# Full_Water_Level_Detector_Project_Schema.net
KiCad netlist of a schematic drawn in EAGLE
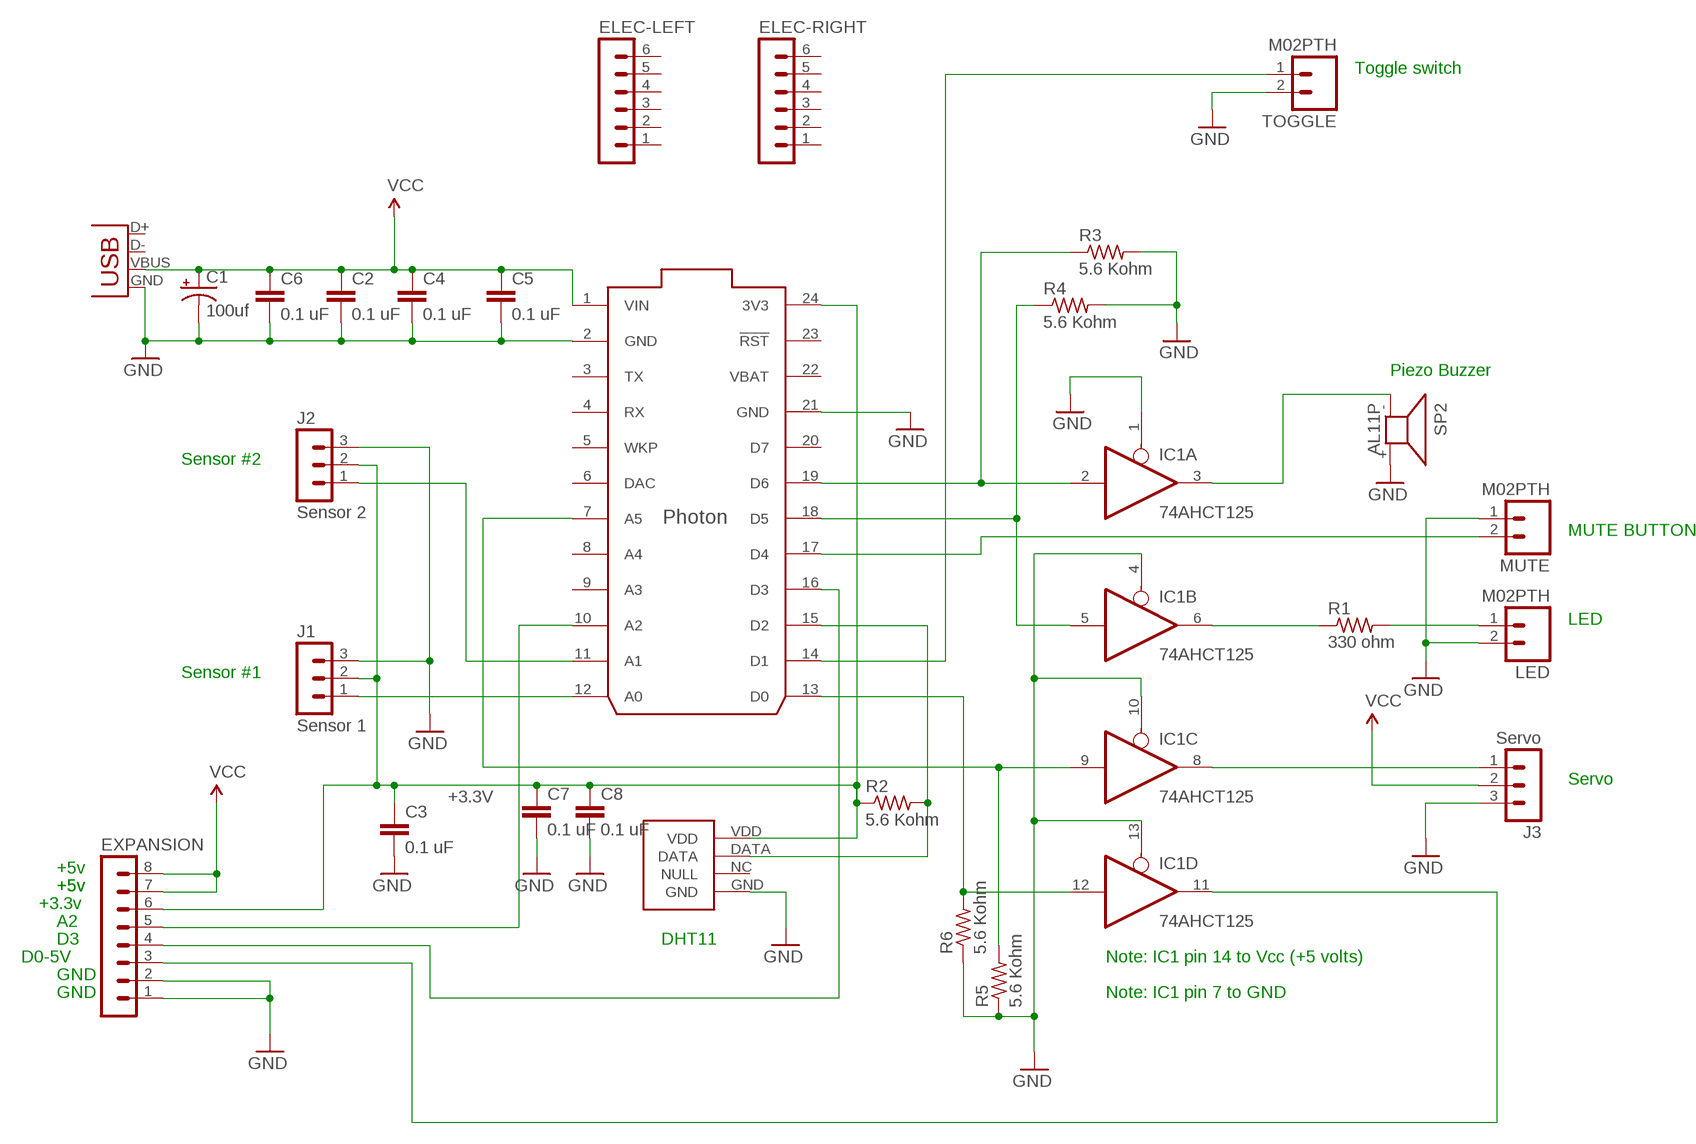
[diagram p0: schematic, sheet 1]

(export (version "E")
  (design (tool "Eeschema 10.0.6"))
  (components
    (comp (ref "C1")
      (value "100uf")
      (footprint "eagle-import:CPOL-RADIAL-100UF-25V")
      (libsource (lib "eagle-import") (part "CAP_POLPTH1"))
    )
    (comp (ref "C2")
      (value "0.1 uF")
      (footprint "eagle-import:CAP-PTH-SMALL")
      (libsource (lib "eagle-import") (part "CAPPTH"))
    )
    (comp (ref "C3")
      (value "0.1 uF")
      (footprint "eagle-import:CAP-PTH-SMALL")
      (libsource (lib "eagle-import") (part "CAPPTH"))
    )
    (comp (ref "C4")
      (value "0.1 uF")
      (footprint "eagle-import:CAP-PTH-SMALL")
      (libsource (lib "eagle-import") (part "CAPPTH"))
    )
    (comp (ref "C5")
      (value "0.1 uF")
      (footprint "eagle-import:CAP-PTH-SMALL")
      (libsource (lib "eagle-import") (part "CAPPTH"))
    )
    (comp (ref "C6")
      (value "0.1 uF")
      (footprint "eagle-import:CAP-PTH-SMALL")
      (libsource (lib "eagle-import") (part "CAPPTH"))
    )
    (comp (ref "C7")
      (value "0.1 uF")
      (footprint "eagle-import:CAP-PTH-SMALL")
      (libsource (lib "eagle-import") (part "CAPPTH"))
    )
    (comp (ref "C8")
      (value "0.1 uF")
      (footprint "eagle-import:CAP-PTH-SMALL")
      (libsource (lib "eagle-import") (part "CAPPTH"))
    )
    (comp (ref "ELEC-LEFT")
      (value "MA06-1")
      (footprint "eagle-import:MA06-1")
      (libsource (lib "eagle-import") (part "MA06-1"))
    )
    (comp (ref "ELEC-RIGHT")
      (value "MA06-1")
      (footprint "eagle-import:MA06-1")
      (libsource (lib "eagle-import") (part "MA06-1"))
    )
    (comp (ref "EXPANSION")
      (value "MA08-1")
      (footprint "eagle-import:MA08-1")
      (libsource (lib "eagle-import") (part "MA08-1"))
    )
    (comp (ref "IC1")
      (value "74AHCT125")
      (footprint "eagle-import:DIL14")
      (libsource (lib "eagle-import") (part "74125N"))
    )
    (comp (ref "J1")
      (value "Sensor 1")
      (footprint "eagle-import:MA03-1")
      (libsource (lib "eagle-import") (part "MA03-1"))
    )
    (comp (ref "J2")
      (value "Sensor 2")
      (footprint "eagle-import:MA03-1")
      (libsource (lib "eagle-import") (part "MA03-1"))
    )
    (comp (ref "J3")
      (value "Servo")
      (footprint "eagle-import:MA03-1")
      (libsource (lib "eagle-import") (part "MA03-1"))
    )
    (comp (ref "JP1")
      (value "USB-B")
      (footprint "eagle-import:USB-B-PTH")
      (libsource (lib "eagle-import") (part "USBPTH"))
    )
    (comp (ref "LED")
      (value "M02PTH")
      (footprint "eagle-import:1X02")
      (libsource (lib "eagle-import") (part "M02PTH"))
    )
    (comp (ref "MUTE")
      (value "M02PTH")
      (footprint "eagle-import:1X02")
      (libsource (lib "eagle-import") (part "M02PTH"))
    )
    (comp (ref "R1")
      (value "330 ohm")
      (footprint "eagle-import:0309_12")
      (libsource (lib "eagle-import") (part "R-US_0309/12"))
    )
    (comp (ref "R2")
      (value "5.6 Kohm")
      (footprint "eagle-import:0309_12")
      (libsource (lib "eagle-import") (part "R-US_0309/12"))
    )
    (comp (ref "R3")
      (value "5.6 Kohm")
      (footprint "eagle-import:0309_12")
      (libsource (lib "eagle-import") (part "R-US_0309/12"))
    )
    (comp (ref "R4")
      (value "5.6 Kohm")
      (footprint "eagle-import:0309_12")
      (libsource (lib "eagle-import") (part "R-US_0309/12"))
    )
    (comp (ref "R5")
      (value "5.6 Kohm")
      (footprint "eagle-import:0309_12")
      (libsource (lib "eagle-import") (part "R-US_0309/12"))
    )
    (comp (ref "R6")
      (value "5.6 Kohm")
      (footprint "eagle-import:0309_12")
      (libsource (lib "eagle-import") (part "R-US_0309/12"))
    )
    (comp (ref "SP2")
      (value "AL11P")
      (footprint "eagle-import:AL11P")
      (libsource (lib "eagle-import") (part "AL11P"))
    )
    (comp (ref "TOGGLE")
      (value "M02PTH")
      (footprint "eagle-import:1X02")
      (libsource (lib "eagle-import") (part "M02PTH"))
    )
    (comp (ref "U$1")
      (value "PHOTON_SMD")
      (footprint "eagle-import:PHOTON_SMD")
      (libsource (lib "eagle-import") (part "PHOTON_SMD"))
    )
    (comp (ref "U$2")
      (value "DHT22")
      (footprint "eagle-import:DHT22")
      (libsource (lib "eagle-import") (part "DHT22"))
    )
  )
  (nets
    (net (code "1") (name "/+3.3V") (class "Default")
      (node (ref "C3") (pin "1") (pinfunction "1_1") (pintype "passive"))
      (node (ref "C7") (pin "1") (pinfunction "1_1") (pintype "passive"))
      (node (ref "C8") (pin "1") (pinfunction "1_1") (pintype "passive"))
      (node (ref "EXPANSION") (pin "6") (pinfunction "6_6") (pintype "passive"))
      (node (ref "J1") (pin "2") (pinfunction "2_2") (pintype "passive"))
      (node (ref "J2") (pin "2") (pinfunction "2_2") (pintype "passive"))
      (node (ref "R2") (pin "1") (pinfunction "1_1") (pintype "passive"))
      (node (ref "U$1") (pin "24") (pinfunction "3V3_24") (pintype "power_in"))
      (node (ref "U$2") (pin "VDD") (pinfunction "VDD_VDD") (pintype "power_in"))
    )
    (net (code "2") (name "/VBAT") (class "Default")
      (node (ref "U$1") (pin "22") (pinfunction "VBAT_22") (pintype "power_in"))
    )
    (net (code "3") (name "GND") (class "Default")
      (node (ref "C1") (pin "2") (pinfunction "-_2") (pintype "passive"))
      (node (ref "C2") (pin "2") (pinfunction "2_2") (pintype "passive"))
      (node (ref "C3") (pin "2") (pinfunction "2_2") (pintype "passive"))
      (node (ref "C4") (pin "2") (pinfunction "2_2") (pintype "passive"))
      (node (ref "C5") (pin "2") (pinfunction "2_2") (pintype "passive"))
      (node (ref "C6") (pin "2") (pinfunction "2_2") (pintype "passive"))
      (node (ref "C7") (pin "2") (pinfunction "2_2") (pintype "passive"))
      (node (ref "C8") (pin "2") (pinfunction "2_2") (pintype "passive"))
      (node (ref "EXPANSION") (pin "1") (pinfunction "1_1") (pintype "passive"))
      (node (ref "EXPANSION") (pin "2") (pinfunction "2_2") (pintype "passive"))
      (node (ref "IC1") (pin "1") (pinfunction "OE_1") (pintype "input"))
      (node (ref "IC1") (pin "10") (pinfunction "OE_10") (pintype "input"))
      (node (ref "IC1") (pin "13") (pinfunction "OE_13") (pintype "input"))
      (node (ref "IC1") (pin "4") (pinfunction "OE_4") (pintype "input"))
      (node (ref "J1") (pin "3") (pinfunction "3_3") (pintype "passive"))
      (node (ref "J2") (pin "3") (pinfunction "3_3") (pintype "passive"))
      (node (ref "J3") (pin "3") (pinfunction "3_3") (pintype "passive"))
      (node (ref "JP1") (pin "GND") (pinfunction "GND_GND") (pintype "bidirectional"))
      (node (ref "LED") (pin "2") (pinfunction "2_2") (pintype "passive"))
      (node (ref "MUTE") (pin "1") (pinfunction "1_1") (pintype "passive"))
      (node (ref "R3") (pin "2") (pinfunction "2_2") (pintype "passive"))
      (node (ref "R4") (pin "2") (pinfunction "2_2") (pintype "passive"))
      (node (ref "R5") (pin "1") (pinfunction "1_1") (pintype "passive"))
      (node (ref "R6") (pin "1") (pinfunction "1_1") (pintype "passive"))
      (node (ref "SP2") (pin "+") (pinfunction "2_+") (pintype "passive"))
      (node (ref "TOGGLE") (pin "2") (pinfunction "2_2") (pintype "passive"))
      (node (ref "U$1") (pin "2") (pinfunction "GND_2") (pintype "power_in"))
      (node (ref "U$1") (pin "21") (pinfunction "GND_21") (pintype "power_in"))
      (node (ref "U$2") (pin "GND") (pinfunction "GND_GND") (pintype "power_in"))
    )
    (net (code "4") (name "Net-(IC1A-I)") (class "Default")
      (node (ref "IC1") (pin "2") (pinfunction "I_2") (pintype "input"))
      (node (ref "R3") (pin "1") (pinfunction "1_1") (pintype "passive"))
      (node (ref "U$1") (pin "19") (pinfunction "D6_19") (pintype "bidirectional"))
    )
    (net (code "5") (name "Net-(IC1A-O)") (class "Default")
      (node (ref "IC1") (pin "3") (pinfunction "O_3") (pintype "tri_state"))
      (node (ref "SP2") (pin "-") (pinfunction "1_-") (pintype "passive"))
    )
    (net (code "6") (name "Net-(IC1B-I)") (class "Default")
      (node (ref "IC1") (pin "5") (pinfunction "I_5") (pintype "input"))
      (node (ref "R4") (pin "1") (pinfunction "1_1") (pintype "passive"))
      (node (ref "U$1") (pin "18") (pinfunction "D5_18") (pintype "bidirectional"))
    )
    (net (code "7") (name "Net-(IC1B-O)") (class "Default")
      (node (ref "IC1") (pin "6") (pinfunction "O_6") (pintype "tri_state"))
      (node (ref "R1") (pin "1") (pinfunction "1_1") (pintype "passive"))
    )
    (net (code "8") (name "Net-(IC1C-I)") (class "Default")
      (node (ref "IC1") (pin "9") (pinfunction "I_9") (pintype "input"))
      (node (ref "R5") (pin "2") (pinfunction "2_2") (pintype "passive"))
      (node (ref "U$1") (pin "7") (pinfunction "A5_7") (pintype "bidirectional"))
    )
    (net (code "9") (name "Net-(IC1C-O)") (class "Default")
      (node (ref "IC1") (pin "8") (pinfunction "O_8") (pintype "tri_state"))
      (node (ref "J3") (pin "1") (pinfunction "1_1") (pintype "passive"))
    )
    (net (code "10") (name "Net-(IC1D-I)") (class "Default")
      (node (ref "IC1") (pin "12") (pinfunction "I_12") (pintype "input"))
      (node (ref "R6") (pin "2") (pinfunction "2_2") (pintype "passive"))
      (node (ref "U$1") (pin "13") (pinfunction "D0_13") (pintype "bidirectional"))
    )
    (net (code "11") (name "Net-(IC1D-O)") (class "Default")
      (node (ref "EXPANSION") (pin "3") (pinfunction "3_3") (pintype "passive"))
      (node (ref "IC1") (pin "11") (pinfunction "O_11") (pintype "tri_state"))
    )
    (net (code "12") (name "Net-(LED-Pad1)") (class "Default")
      (node (ref "LED") (pin "1") (pinfunction "1_1") (pintype "passive"))
      (node (ref "R1") (pin "2") (pinfunction "2_2") (pintype "passive"))
    )
    (net (code "13") (name "Net-(U$1A-A0)") (class "Default")
      (node (ref "J1") (pin "1") (pinfunction "1_1") (pintype "passive"))
      (node (ref "U$1") (pin "12") (pinfunction "A0_12") (pintype "bidirectional"))
    )
    (net (code "14") (name "Net-(U$1A-A1)") (class "Default")
      (node (ref "J2") (pin "1") (pinfunction "1_1") (pintype "passive"))
      (node (ref "U$1") (pin "11") (pinfunction "A1_11") (pintype "bidirectional"))
    )
    (net (code "15") (name "Net-(U$1A-A2)") (class "Default")
      (node (ref "EXPANSION") (pin "5") (pinfunction "5_5") (pintype "passive"))
      (node (ref "U$1") (pin "10") (pinfunction "A2_10") (pintype "bidirectional"))
    )
    (net (code "16") (name "Net-(U$1A-D1)") (class "Default")
      (node (ref "TOGGLE") (pin "1") (pinfunction "1_1") (pintype "passive"))
      (node (ref "U$1") (pin "14") (pinfunction "D1_14") (pintype "bidirectional"))
    )
    (net (code "17") (name "Net-(U$1A-D2)") (class "Default")
      (node (ref "R2") (pin "2") (pinfunction "2_2") (pintype "passive"))
      (node (ref "U$1") (pin "15") (pinfunction "D2_15") (pintype "bidirectional"))
      (node (ref "U$2") (pin "DATA") (pinfunction "DATA_DATA") (pintype "output"))
    )
    (net (code "18") (name "Net-(U$1A-D3)") (class "Default")
      (node (ref "EXPANSION") (pin "4") (pinfunction "4_4") (pintype "passive"))
      (node (ref "U$1") (pin "16") (pinfunction "D3_16") (pintype "bidirectional"))
    )
    (net (code "19") (name "Net-(U$1A-D4)") (class "Default")
      (node (ref "MUTE") (pin "2") (pinfunction "2_2") (pintype "passive"))
      (node (ref "U$1") (pin "17") (pinfunction "D4_17") (pintype "bidirectional"))
    )
    (net (code "20") (name "VCC") (class "Default")
      (node (ref "C1") (pin "1") (pinfunction "+_1") (pintype "passive"))
      (node (ref "C2") (pin "1") (pinfunction "1_1") (pintype "passive"))
      (node (ref "C4") (pin "1") (pinfunction "1_1") (pintype "passive"))
      (node (ref "C5") (pin "1") (pinfunction "1_1") (pintype "passive"))
      (node (ref "C6") (pin "1") (pinfunction "1_1") (pintype "passive"))
      (node (ref "EXPANSION") (pin "7") (pinfunction "7_7") (pintype "passive"))
      (node (ref "EXPANSION") (pin "8") (pinfunction "8_8") (pintype "passive"))
      (node (ref "J3") (pin "2") (pinfunction "2_2") (pintype "passive"))
      (node (ref "JP1") (pin "VBUS") (pinfunction "VBUS_VBUS") (pintype "bidirectional"))
      (node (ref "U$1") (pin "1") (pinfunction "VIN_1") (pintype "power_in"))
    )
    (net (code "21") (name "unconnected-(ELEC-LEFT-Pad1)") (class "Default")
      (node (ref "ELEC-LEFT") (pin "1") (pinfunction "1_1") (pintype "passive"))
    )
    (net (code "22") (name "unconnected-(ELEC-LEFT-Pad2)") (class "Default")
      (node (ref "ELEC-LEFT") (pin "2") (pinfunction "2_2") (pintype "passive"))
    )
    (net (code "23") (name "unconnected-(ELEC-LEFT-Pad3)") (class "Default")
      (node (ref "ELEC-LEFT") (pin "3") (pinfunction "3_3") (pintype "passive"))
    )
    (net (code "24") (name "unconnected-(ELEC-LEFT-Pad4)") (class "Default")
      (node (ref "ELEC-LEFT") (pin "4") (pinfunction "4_4") (pintype "passive"))
    )
    (net (code "25") (name "unconnected-(ELEC-LEFT-Pad5)") (class "Default")
      (node (ref "ELEC-LEFT") (pin "5") (pinfunction "5_5") (pintype "passive"))
    )
    (net (code "26") (name "unconnected-(ELEC-LEFT-Pad6)") (class "Default")
      (node (ref "ELEC-LEFT") (pin "6") (pinfunction "6_6") (pintype "passive"))
    )
    (net (code "27") (name "unconnected-(ELEC-RIGHT-Pad1)") (class "Default")
      (node (ref "ELEC-RIGHT") (pin "1") (pinfunction "1_1") (pintype "passive"))
    )
    (net (code "28") (name "unconnected-(ELEC-RIGHT-Pad2)") (class "Default")
      (node (ref "ELEC-RIGHT") (pin "2") (pinfunction "2_2") (pintype "passive"))
    )
    (net (code "29") (name "unconnected-(ELEC-RIGHT-Pad3)") (class "Default")
      (node (ref "ELEC-RIGHT") (pin "3") (pinfunction "3_3") (pintype "passive"))
    )
    (net (code "30") (name "unconnected-(ELEC-RIGHT-Pad4)") (class "Default")
      (node (ref "ELEC-RIGHT") (pin "4") (pinfunction "4_4") (pintype "passive"))
    )
    (net (code "31") (name "unconnected-(ELEC-RIGHT-Pad5)") (class "Default")
      (node (ref "ELEC-RIGHT") (pin "5") (pinfunction "5_5") (pintype "passive"))
    )
    (net (code "32") (name "unconnected-(ELEC-RIGHT-Pad6)") (class "Default")
      (node (ref "ELEC-RIGHT") (pin "6") (pinfunction "6_6") (pintype "passive"))
    )
    (net (code "33") (name "unconnected-(JP1-PadD+)") (class "Default")
      (node (ref "JP1") (pin "D+") (pinfunction "D+_D+") (pintype "bidirectional"))
    )
    (net (code "34") (name "unconnected-(JP1-PadD-)") (class "Default")
      (node (ref "JP1") (pin "D-") (pinfunction "D-_D-") (pintype "bidirectional"))
    )
    (net (code "35") (name "unconnected-(U$1A-A3-Pad9)") (class "Default")
      (node (ref "U$1") (pin "9") (pinfunction "A3_9") (pintype "bidirectional"))
    )
    (net (code "36") (name "unconnected-(U$1A-A4-Pad8)") (class "Default")
      (node (ref "U$1") (pin "8") (pinfunction "A4_8") (pintype "bidirectional"))
    )
    (net (code "37") (name "unconnected-(U$1A-D7-Pad20)") (class "Default")
      (node (ref "U$1") (pin "20") (pinfunction "D7_20") (pintype "bidirectional"))
    )
    (net (code "38") (name "unconnected-(U$1A-DAC-Pad6)") (class "Default")
      (node (ref "U$1") (pin "6") (pinfunction "DAC_6") (pintype "bidirectional"))
    )
    (net (code "39") (name "unconnected-(U$1A-RX-Pad4)") (class "Default")
      (node (ref "U$1") (pin "4") (pinfunction "RX_4") (pintype "bidirectional"))
    )
    (net (code "40") (name "unconnected-(U$1A-TX-Pad3)") (class "Default")
      (node (ref "U$1") (pin "3") (pinfunction "TX_3") (pintype "bidirectional"))
    )
    (net (code "41") (name "unconnected-(U$1A-WKP-Pad5)") (class "Default")
      (node (ref "U$1") (pin "5") (pinfunction "WKP_5") (pintype "bidirectional"))
    )
    (net (code "42") (name "unconnected-(U$1A-~{RST}-Pad23)") (class "Default")
      (node (ref "U$1") (pin "23") (pinfunction "~{RST}_23") (pintype "bidirectional"))
    )
    (net (code "43") (name "unconnected-(U$2-NULL-PadNC)") (class "Default")
      (node (ref "U$2") (pin "NC") (pinfunction "NULL_NC") (pintype "no_connect"))
    )
  )
)
